# sensores.net
KiCad netlist of a schematic drawn in EAGLE
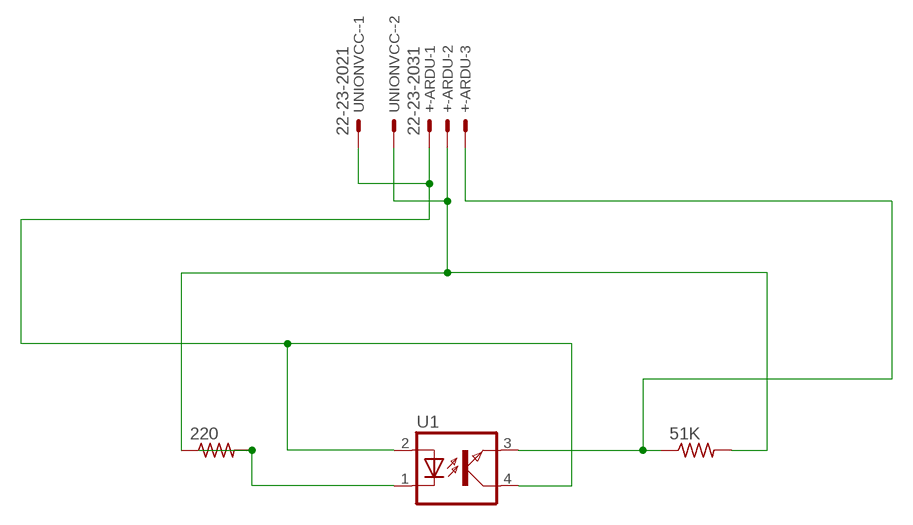
[diagram p0: schematic, sheet 1]

(export (version "E")
  (design (tool "Eeschema 10.0.6"))
  (components
    (comp (ref "+-ARDU")
      (value "22-23-2031")
      (footprint "eagle-import:22-23-2031")
      (fields (field (name "MF") "MOLEX"))
      (libsource (lib "eagle-import") (part "22-23-2031"))
    )
    (comp (ref "51K")
      (value "R-US_0207/10")
      (footprint "eagle-import:0207_10")
      (libsource (lib "eagle-import") (part "R-US_0207/10"))
    )
    (comp (ref "220")
      (value "R-US_0207/10")
      (footprint "eagle-import:0207_10")
      (libsource (lib "eagle-import") (part "R-US_0207/10"))
    )
    (comp (ref "U1")
      (value "CNY70")
      (footprint "eagle-import:CNY70")
      (libsource (lib "eagle-import") (part "CNY70"))
    )
    (comp (ref "UNIONVCC-")
      (value "22-23-2021")
      (footprint "eagle-import:22-23-2021")
      (fields (field (name "MF") "MOLEX"))
      (libsource (lib "eagle-import") (part "22-23-2021"))
    )
  )
  (nets
    (net (code "1") (name "Net-(+-ARDUA-S)") (class "Default")
      (node (ref "+-ARDU") (pin "1") (pinfunction "S_1") (pintype "passive"))
      (node (ref "U1") (pin "2") (pinfunction "2_2") (pintype "passive"))
      (node (ref "U1") (pin "4") (pinfunction "4_4") (pintype "passive"))
      (node (ref "UNIONVCC-") (pin "1") (pinfunction "S_1") (pintype "passive"))
    )
    (net (code "2") (name "Net-(+-ARDUB-S)") (class "Default")
      (node (ref "+-ARDU") (pin "2") (pinfunction "S_2") (pintype "passive"))
      (node (ref "220") (pin "1") (pinfunction "1_1") (pintype "passive"))
      (node (ref "51K") (pin "2") (pinfunction "2_2") (pintype "passive"))
      (node (ref "UNIONVCC-") (pin "2") (pinfunction "S_2") (pintype "passive"))
    )
    (net (code "3") (name "Net-(+-ARDUC-S)") (class "Default")
      (node (ref "+-ARDU") (pin "3") (pinfunction "S_3") (pintype "passive"))
      (node (ref "51K") (pin "1") (pinfunction "1_1") (pintype "passive"))
      (node (ref "U1") (pin "3") (pinfunction "3_3") (pintype "passive"))
    )
    (net (code "4") (name "Net-(220-Pad2)") (class "Default")
      (node (ref "220") (pin "2") (pinfunction "2_2") (pintype "passive"))
      (node (ref "U1") (pin "1") (pinfunction "1_1") (pintype "passive"))
    )
  )
)
